# PROC099B_SOP_Headers_Reference.net
KiCad netlist of a schematic drawn in Altium Designer
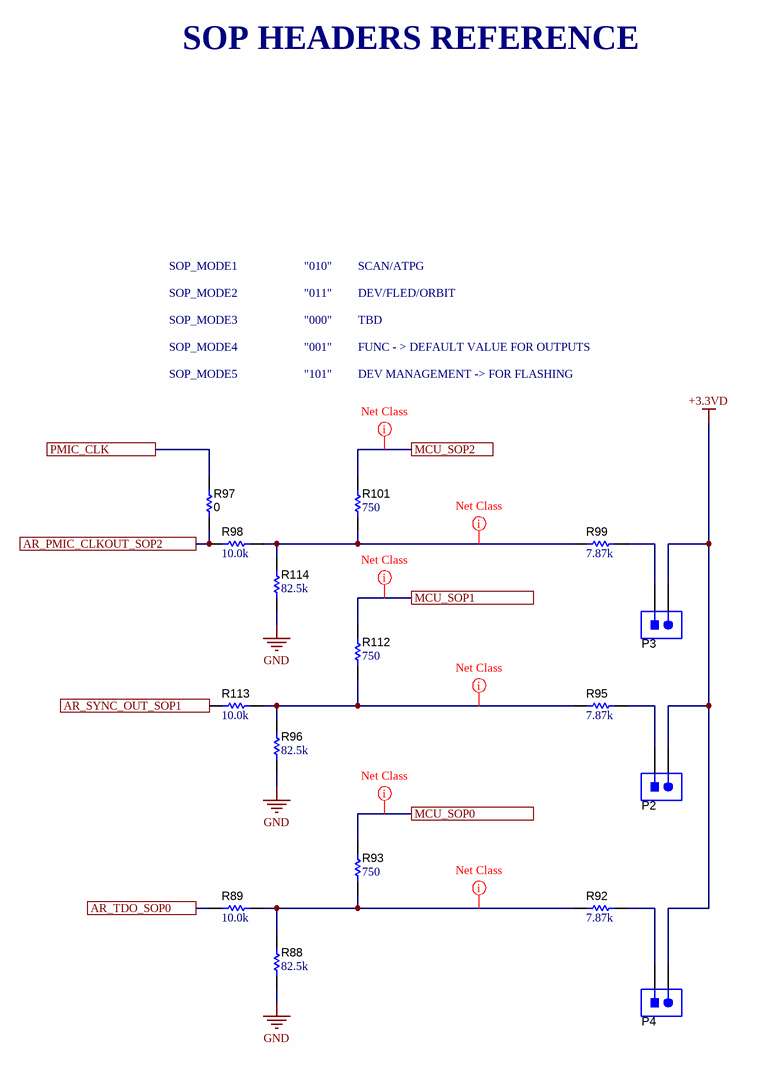
[diagram p0: PROC099B_SOP_Headers_Reference.SchDoc]

(export (version "E")
  (design (tool "Eeschema 10.0.6"))
  (components
    (comp (ref "P2")
      (value "TSW-102-07-G-S")
      (footprint "TSW-102-07-G-S")
      (description "Header, 100mil, 2x1, Gold, TH")
      (fields (field (name "MANUFACTURER") "Samtec"))
      (libsource (lib "Altium Vault - TI") (part "CMP-0075405-2"))
    )
    (comp (ref "P3")
      (value "TSW-102-07-G-S")
      (footprint "TSW-102-07-G-S")
      (description "Header, 100mil, 2x1, Gold, TH")
      (fields (field (name "MANUFACTURER") "Samtec"))
      (libsource (lib "Altium Vault - TI") (part "CMP-0075405-2"))
    )
    (comp (ref "P4")
      (value "TSW-102-07-G-S")
      (footprint "TSW-102-07-G-S")
      (description "Header, 100mil, 2x1, Gold, TH")
      (fields (field (name "MANUFACTURER") "Samtec"))
      (libsource (lib "Altium Vault - TI") (part "CMP-0075405-2"))
    )
    (comp (ref "R88")
      (value "CRCW040282K5FKED")
      (footprint "0402L")
      (description "RES, 82.5 k, 1%, 0.063 W, AEC-Q200 Grade 0, 0402")
      (fields (field (name "MANUFACTURER") "Vishay-Dale") (field (name "VALUEDISPLAYED") "82.5k"))
      (libsource (lib "Altium Vault - TI") (part "Resistor"))
    )
    (comp (ref "R89")
      (value "CRCW040210K0FKED")
      (footprint "0402L")
      (description "RES, 10.0 k, 1%, 0.063 W, AEC-Q200 Grade 0, 0402")
      (fields (field (name "MANUFACTURER") "Vishay-Dale") (field (name "VALUEDISPLAYED") "10.0k"))
      (libsource (lib "Altium Vault - TI") (part "CMP-0025958-3"))
    )
    (comp (ref "R92")
      (value "CRCW04027K87FKED")
      (footprint "0402L")
      (description "RES, 7.87 k, 1%, 0.063 W, AEC-Q200 Grade 0, 0402")
      (fields (field (name "MANUFACTURER") "Vishay-Dale") (field (name "VALUEDISPLAYED") "7.87k"))
      (libsource (lib "Altium Vault - TI") (part "Resistor"))
    )
    (comp (ref "R93")
      (value "CRCW0402750RFKED")
      (footprint "0402L")
      (description "RES, 750, 1%, 0.063 W, AEC-Q200 Grade 0, 0402")
      (fields (field (name "MANUFACTURER") "Vishay-Dale") (field (name "VALUEDISPLAYED") "750"))
      (libsource (lib "Altium Vault - TI") (part "Resistor"))
    )
    (comp (ref "R95")
      (value "CRCW04027K87FKED")
      (footprint "0402L")
      (description "RES, 7.87 k, 1%, 0.063 W, AEC-Q200 Grade 0, 0402")
      (fields (field (name "MANUFACTURER") "Vishay-Dale") (field (name "VALUEDISPLAYED") "7.87k"))
      (libsource (lib "Altium Vault - TI") (part "Resistor"))
    )
    (comp (ref "R96")
      (value "CRCW040282K5FKED")
      (footprint "0402L")
      (description "RES, 82.5 k, 1%, 0.063 W, AEC-Q200 Grade 0, 0402")
      (fields (field (name "MANUFACTURER") "Vishay-Dale") (field (name "VALUEDISPLAYED") "82.5k"))
      (libsource (lib "Altium Vault - TI") (part "Resistor"))
    )
    (comp (ref "R97")
      (value "ERJ-2GE0R00X")
      (footprint "0402L")
      (description "RES, 0, 5%, 0.063 W, 0402")
      (fields
        (field (name "MANUFACTURER") "Panasonic")
        (field (name "VALUEDISPLAYED") "0")
        (field (name "PUBLISHER") "Texas Instruments")
      )
      (libsource (lib "Altium Vault - TI") (part "CMP-0026992-2"))
    )
    (comp (ref "R98")
      (value "CRCW040210K0FKED")
      (footprint "0402L")
      (description "RES, 10.0 k, 1%, 0.063 W, AEC-Q200 Grade 0, 0402")
      (fields (field (name "MANUFACTURER") "Vishay-Dale") (field (name "VALUEDISPLAYED") "10.0k"))
      (libsource (lib "Altium Vault - TI") (part "CMP-0025958-3"))
    )
    (comp (ref "R99")
      (value "CRCW04027K87FKED")
      (footprint "0402L")
      (description "RES, 7.87 k, 1%, 0.063 W, AEC-Q200 Grade 0, 0402")
      (fields (field (name "MANUFACTURER") "Vishay-Dale") (field (name "VALUEDISPLAYED") "7.87k"))
      (libsource (lib "Altium Vault - TI") (part "Resistor"))
    )
    (comp (ref "R101")
      (value "CRCW0402750RFKED")
      (footprint "0402L")
      (description "RES, 750, 1%, 0.063 W, AEC-Q200 Grade 0, 0402")
      (fields (field (name "MANUFACTURER") "Vishay-Dale") (field (name "VALUEDISPLAYED") "750"))
      (libsource (lib "Altium Vault - TI") (part "CMP-0026542-2"))
    )
    (comp (ref "R112")
      (value "CRCW0402750RFKED")
      (footprint "0402L")
      (description "RES, 750, 1%, 0.063 W, AEC-Q200 Grade 0, 0402")
      (fields (field (name "MANUFACTURER") "Vishay-Dale") (field (name "VALUEDISPLAYED") "750"))
      (libsource (lib "Altium Vault - TI") (part "Resistor"))
    )
    (comp (ref "R113")
      (value "CRCW040210K0FKED")
      (footprint "0402L")
      (description "RES, 10.0 k, 1%, 0.063 W, AEC-Q200 Grade 0, 0402")
      (fields (field (name "MANUFACTURER") "Vishay-Dale") (field (name "VALUEDISPLAYED") "10.0k"))
      (libsource (lib "Altium Vault - TI") (part "CMP-0025958-3"))
    )
    (comp (ref "R114")
      (value "CRCW040282K5FKED")
      (footprint "0402L")
      (description "RES, 82.5 k, 1%, 0.063 W, AEC-Q200 Grade 0, 0402")
      (fields (field (name "MANUFACTURER") "Vishay-Dale") (field (name "VALUEDISPLAYED") "82.5k"))
      (libsource (lib "Altium Vault - TI") (part "CMP-0026574-2"))
    )
  )
  (nets
    (net (code "1") (name "+3.3VD") (class "Default")
      (node (ref "P2") (pin "2") (pinfunction "2_2") (pintype "passive"))
      (node (ref "P3") (pin "2") (pinfunction "2_2") (pintype "passive"))
      (node (ref "P4") (pin "2") (pinfunction "2_2") (pintype "passive"))
    )
    (net (code "2") (name "/AR_PMIC_CLKOUT_SOP2") (class "Default")
      (node (ref "R97") (pin "1") (pinfunction "1_1") (pintype "passive"))
      (node (ref "R98") (pin "1") (pinfunction "1_1") (pintype "passive"))
    )
    (net (code "3") (name "/AR_SYNC_OUT_SOP1") (class "Default")
      (node (ref "R113") (pin "1") (pinfunction "1_1") (pintype "passive"))
    )
    (net (code "4") (name "/AR_TDO_SOP0") (class "Default")
      (node (ref "R89") (pin "1") (pinfunction "1_1") (pintype "passive"))
    )
    (net (code "5") (name "/MCU_SOP0") (class "Default")
      (node (ref "R93") (pin "2") (pinfunction "2_2") (pintype "passive"))
    )
    (net (code "6") (name "/MCU_SOP1") (class "Default")
      (node (ref "R112") (pin "2") (pinfunction "2_2") (pintype "passive"))
    )
    (net (code "7") (name "/MCU_SOP2") (class "Default")
      (node (ref "R101") (pin "2") (pinfunction "2_2") (pintype "passive"))
    )
    (net (code "8") (name "/PMIC_CLK") (class "Default")
      (node (ref "R97") (pin "2") (pinfunction "2_2") (pintype "passive"))
    )
    (net (code "9") (name "GND") (class "Default")
      (node (ref "R114") (pin "1") (pinfunction "1_1") (pintype "passive"))
      (node (ref "R88") (pin "1") (pinfunction "1_1") (pintype "passive"))
      (node (ref "R96") (pin "1") (pinfunction "1_1") (pintype "passive"))
    )
    (net (code "10") (name "Net-(P2-Pad1)") (class "Default")
      (node (ref "P2") (pin "1") (pinfunction "1_1") (pintype "passive"))
      (node (ref "R95") (pin "2") (pinfunction "2_2") (pintype "passive"))
    )
    (net (code "11") (name "Net-(P3-Pad1)") (class "Default")
      (node (ref "P3") (pin "1") (pinfunction "1_1") (pintype "passive"))
      (node (ref "R99") (pin "2") (pinfunction "2_2") (pintype "passive"))
    )
    (net (code "12") (name "Net-(P4-Pad1)") (class "Default")
      (node (ref "P4") (pin "1") (pinfunction "1_1") (pintype "passive"))
      (node (ref "R92") (pin "2") (pinfunction "2_2") (pintype "passive"))
    )
    (net (code "13") (name "Net-(R88-Pad2)") (class "Default")
      (node (ref "R88") (pin "2") (pinfunction "2_2") (pintype "passive"))
      (node (ref "R89") (pin "2") (pinfunction "2_2") (pintype "passive"))
      (node (ref "R92") (pin "1") (pinfunction "1_1") (pintype "passive"))
      (node (ref "R93") (pin "1") (pinfunction "1_1") (pintype "passive"))
    )
    (net (code "14") (name "Net-(R101-Pad1)") (class "Default")
      (node (ref "R101") (pin "1") (pinfunction "1_1") (pintype "passive"))
      (node (ref "R114") (pin "2") (pinfunction "2_2") (pintype "passive"))
      (node (ref "R98") (pin "2") (pinfunction "2_2") (pintype "passive"))
      (node (ref "R99") (pin "1") (pinfunction "1_1") (pintype "passive"))
    )
    (net (code "15") (name "Net-(R112-Pad1)") (class "Default")
      (node (ref "R112") (pin "1") (pinfunction "1_1") (pintype "passive"))
      (node (ref "R113") (pin "2") (pinfunction "2_2") (pintype "passive"))
      (node (ref "R95") (pin "1") (pinfunction "1_1") (pintype "passive"))
      (node (ref "R96") (pin "2") (pinfunction "2_2") (pintype "passive"))
    )
  )
)
